# 16ch_omn_hirose_adapter.net
KiCad netlist of a schematic drawn in EAGLE
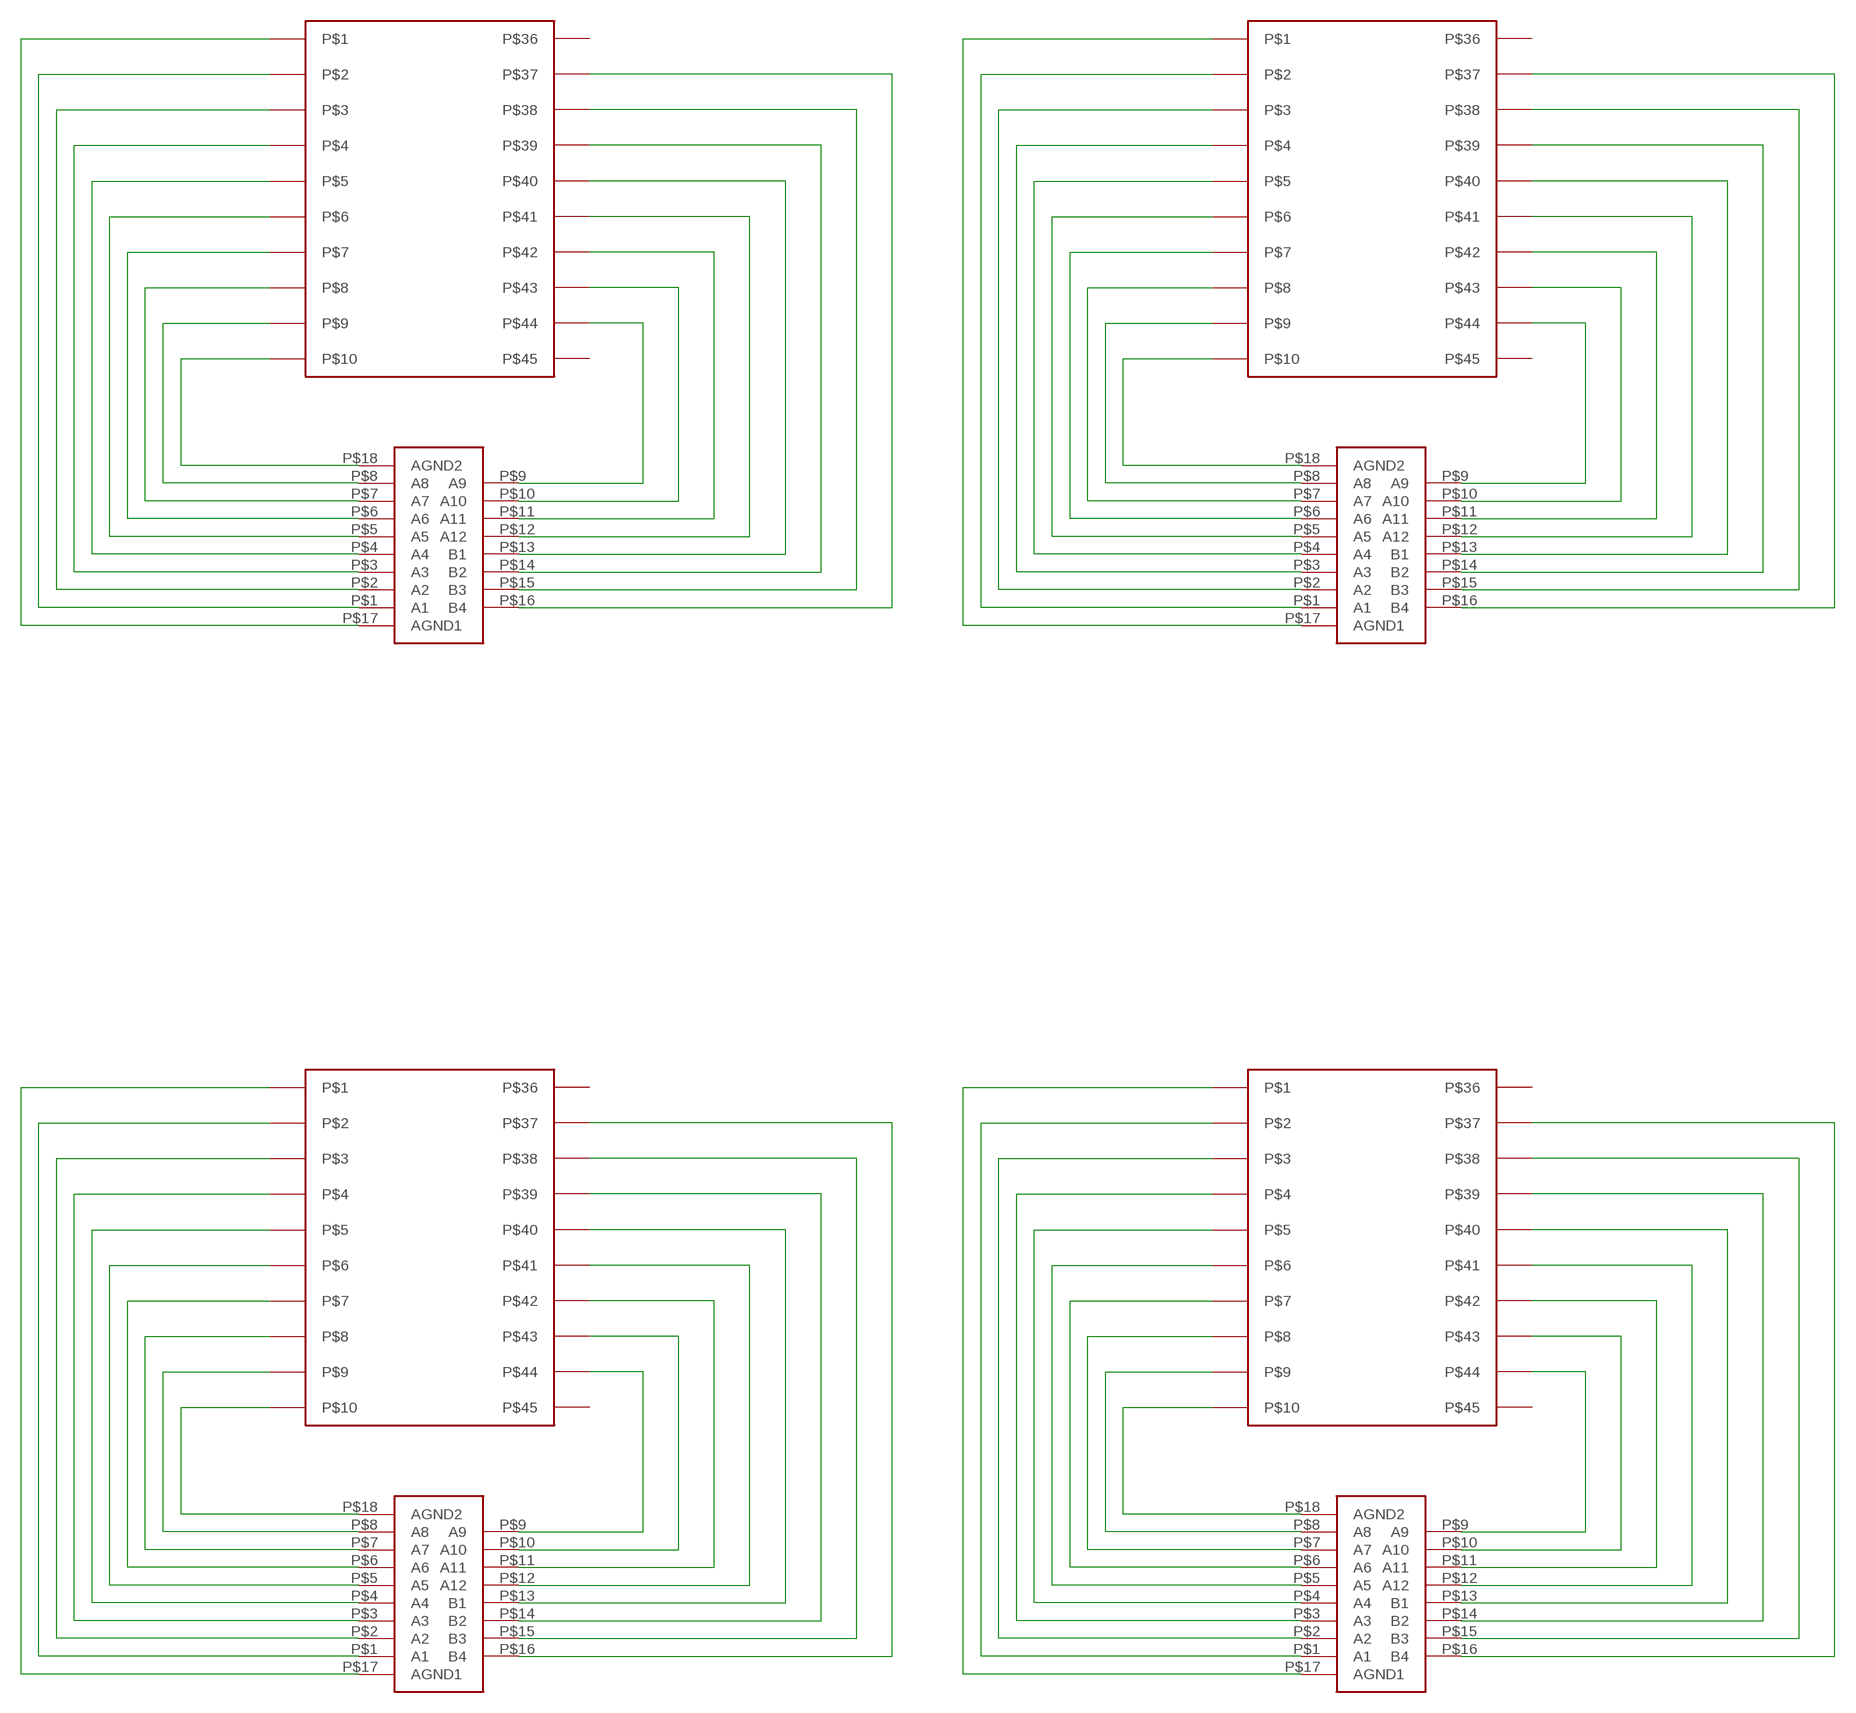
[diagram p0: schematic, sheet 1]

(export (version "E")
  (design (tool "Eeschema 10.0.6"))
  (components
    (comp (ref "U$1")
      (value "HIROSE_DF40_70PIN")
      (footprint "eagle-import:HIROSE_DF40C-70DS")
      (libsource (lib "eagle-import") (part "HIROSE_DF40_70PIN"))
    )
    (comp (ref "U$2")
      (value "OMNETICS_FE18")
      (footprint "eagle-import:OMNETICS_FE18")
      (libsource (lib "eagle-import") (part "OMNETICS_FE18"))
    )
    (comp (ref "U$3")
      (value "HIROSE_DF40_70PIN")
      (footprint "eagle-import:HIROSE_DF40C-70DS")
      (libsource (lib "eagle-import") (part "HIROSE_DF40_70PIN"))
    )
    (comp (ref "U$4")
      (value "OMNETICS_FE18")
      (footprint "eagle-import:OMNETICS_FE18")
      (libsource (lib "eagle-import") (part "OMNETICS_FE18"))
    )
    (comp (ref "U$5")
      (value "HIROSE_DF40_70PIN")
      (footprint "eagle-import:HIROSE_DF40C-70DS")
      (libsource (lib "eagle-import") (part "HIROSE_DF40_70PIN"))
    )
    (comp (ref "U$6")
      (value "OMNETICS_FE18")
      (footprint "eagle-import:OMNETICS_FE18")
      (libsource (lib "eagle-import") (part "OMNETICS_FE18"))
    )
    (comp (ref "U$7")
      (value "HIROSE_DF40_70PIN")
      (footprint "eagle-import:HIROSE_DF40C-70DS")
      (libsource (lib "eagle-import") (part "HIROSE_DF40_70PIN"))
    )
    (comp (ref "U$8")
      (value "OMNETICS_FE18")
      (footprint "eagle-import:OMNETICS_FE18")
      (libsource (lib "eagle-import") (part "OMNETICS_FE18"))
    )
  )
  (nets
    (net (code "1") (name "Net-(U$2-A1)") (class "Default")
      (node (ref "U$1") (pin "P$2") (pinfunction "P$2_P$2") (pintype "bidirectional"))
      (node (ref "U$2") (pin "P$1") (pinfunction "A1_P$1") (pintype "bidirectional"))
    )
    (net (code "2") (name "Net-(U$2-A2)") (class "Default")
      (node (ref "U$1") (pin "P$3") (pinfunction "P$3_P$3") (pintype "bidirectional"))
      (node (ref "U$2") (pin "P$2") (pinfunction "A2_P$2") (pintype "bidirectional"))
    )
    (net (code "3") (name "Net-(U$2-A3)") (class "Default")
      (node (ref "U$1") (pin "P$4") (pinfunction "P$4_P$4") (pintype "bidirectional"))
      (node (ref "U$2") (pin "P$3") (pinfunction "A3_P$3") (pintype "bidirectional"))
    )
    (net (code "4") (name "Net-(U$2-A4)") (class "Default")
      (node (ref "U$1") (pin "P$5") (pinfunction "P$5_P$5") (pintype "bidirectional"))
      (node (ref "U$2") (pin "P$4") (pinfunction "A4_P$4") (pintype "bidirectional"))
    )
    (net (code "5") (name "Net-(U$2-A5)") (class "Default")
      (node (ref "U$1") (pin "P$6") (pinfunction "P$6_P$6") (pintype "bidirectional"))
      (node (ref "U$2") (pin "P$5") (pinfunction "A5_P$5") (pintype "bidirectional"))
    )
    (net (code "6") (name "Net-(U$2-A6)") (class "Default")
      (node (ref "U$1") (pin "P$7") (pinfunction "P$7_P$7") (pintype "bidirectional"))
      (node (ref "U$2") (pin "P$6") (pinfunction "A6_P$6") (pintype "bidirectional"))
    )
    (net (code "7") (name "Net-(U$2-A7)") (class "Default")
      (node (ref "U$1") (pin "P$8") (pinfunction "P$8_P$8") (pintype "bidirectional"))
      (node (ref "U$2") (pin "P$7") (pinfunction "A7_P$7") (pintype "bidirectional"))
    )
    (net (code "8") (name "Net-(U$2-A8)") (class "Default")
      (node (ref "U$1") (pin "P$9") (pinfunction "P$9_P$9") (pintype "bidirectional"))
      (node (ref "U$2") (pin "P$8") (pinfunction "A8_P$8") (pintype "bidirectional"))
    )
    (net (code "9") (name "Net-(U$2-A9)") (class "Default")
      (node (ref "U$1") (pin "P$44") (pinfunction "P$44_P$44") (pintype "bidirectional"))
      (node (ref "U$2") (pin "P$9") (pinfunction "A9_P$9") (pintype "bidirectional"))
    )
    (net (code "10") (name "Net-(U$2-A10)") (class "Default")
      (node (ref "U$1") (pin "P$43") (pinfunction "P$43_P$43") (pintype "bidirectional"))
      (node (ref "U$2") (pin "P$10") (pinfunction "A10_P$10") (pintype "bidirectional"))
    )
    (net (code "11") (name "Net-(U$2-A11)") (class "Default")
      (node (ref "U$1") (pin "P$42") (pinfunction "P$42_P$42") (pintype "bidirectional"))
      (node (ref "U$2") (pin "P$11") (pinfunction "A11_P$11") (pintype "bidirectional"))
    )
    (net (code "12") (name "Net-(U$2-A12)") (class "Default")
      (node (ref "U$1") (pin "P$41") (pinfunction "P$41_P$41") (pintype "bidirectional"))
      (node (ref "U$2") (pin "P$12") (pinfunction "A12_P$12") (pintype "bidirectional"))
    )
    (net (code "13") (name "Net-(U$2-AGND1)") (class "Default")
      (node (ref "U$1") (pin "P$1") (pinfunction "P$1_P$1") (pintype "bidirectional"))
      (node (ref "U$2") (pin "P$17") (pinfunction "AGND1_P$17") (pintype "bidirectional"))
    )
    (net (code "14") (name "Net-(U$2-AGND2)") (class "Default")
      (node (ref "U$1") (pin "P$10") (pinfunction "P$10_P$10") (pintype "bidirectional"))
      (node (ref "U$2") (pin "P$18") (pinfunction "AGND2_P$18") (pintype "bidirectional"))
    )
    (net (code "15") (name "Net-(U$2-B1)") (class "Default")
      (node (ref "U$1") (pin "P$40") (pinfunction "P$40_P$40") (pintype "bidirectional"))
      (node (ref "U$2") (pin "P$13") (pinfunction "B1_P$13") (pintype "bidirectional"))
    )
    (net (code "16") (name "Net-(U$2-B2)") (class "Default")
      (node (ref "U$1") (pin "P$39") (pinfunction "P$39_P$39") (pintype "bidirectional"))
      (node (ref "U$2") (pin "P$14") (pinfunction "B2_P$14") (pintype "bidirectional"))
    )
    (net (code "17") (name "Net-(U$2-B3)") (class "Default")
      (node (ref "U$1") (pin "P$38") (pinfunction "P$38_P$38") (pintype "bidirectional"))
      (node (ref "U$2") (pin "P$15") (pinfunction "B3_P$15") (pintype "bidirectional"))
    )
    (net (code "18") (name "Net-(U$2-B4)") (class "Default")
      (node (ref "U$1") (pin "P$37") (pinfunction "P$37_P$37") (pintype "bidirectional"))
      (node (ref "U$2") (pin "P$16") (pinfunction "B4_P$16") (pintype "bidirectional"))
    )
    (net (code "19") (name "Net-(U$4-A1)") (class "Default")
      (node (ref "U$3") (pin "P$2") (pinfunction "P$2_P$2") (pintype "bidirectional"))
      (node (ref "U$4") (pin "P$1") (pinfunction "A1_P$1") (pintype "bidirectional"))
    )
    (net (code "20") (name "Net-(U$4-A2)") (class "Default")
      (node (ref "U$3") (pin "P$3") (pinfunction "P$3_P$3") (pintype "bidirectional"))
      (node (ref "U$4") (pin "P$2") (pinfunction "A2_P$2") (pintype "bidirectional"))
    )
    (net (code "21") (name "Net-(U$4-A3)") (class "Default")
      (node (ref "U$3") (pin "P$4") (pinfunction "P$4_P$4") (pintype "bidirectional"))
      (node (ref "U$4") (pin "P$3") (pinfunction "A3_P$3") (pintype "bidirectional"))
    )
    (net (code "22") (name "Net-(U$4-A4)") (class "Default")
      (node (ref "U$3") (pin "P$5") (pinfunction "P$5_P$5") (pintype "bidirectional"))
      (node (ref "U$4") (pin "P$4") (pinfunction "A4_P$4") (pintype "bidirectional"))
    )
    (net (code "23") (name "Net-(U$4-A5)") (class "Default")
      (node (ref "U$3") (pin "P$6") (pinfunction "P$6_P$6") (pintype "bidirectional"))
      (node (ref "U$4") (pin "P$5") (pinfunction "A5_P$5") (pintype "bidirectional"))
    )
    (net (code "24") (name "Net-(U$4-A6)") (class "Default")
      (node (ref "U$3") (pin "P$7") (pinfunction "P$7_P$7") (pintype "bidirectional"))
      (node (ref "U$4") (pin "P$6") (pinfunction "A6_P$6") (pintype "bidirectional"))
    )
    (net (code "25") (name "Net-(U$4-A7)") (class "Default")
      (node (ref "U$3") (pin "P$8") (pinfunction "P$8_P$8") (pintype "bidirectional"))
      (node (ref "U$4") (pin "P$7") (pinfunction "A7_P$7") (pintype "bidirectional"))
    )
    (net (code "26") (name "Net-(U$4-A8)") (class "Default")
      (node (ref "U$3") (pin "P$9") (pinfunction "P$9_P$9") (pintype "bidirectional"))
      (node (ref "U$4") (pin "P$8") (pinfunction "A8_P$8") (pintype "bidirectional"))
    )
    (net (code "27") (name "Net-(U$4-A9)") (class "Default")
      (node (ref "U$3") (pin "P$44") (pinfunction "P$44_P$44") (pintype "bidirectional"))
      (node (ref "U$4") (pin "P$9") (pinfunction "A9_P$9") (pintype "bidirectional"))
    )
    (net (code "28") (name "Net-(U$4-A10)") (class "Default")
      (node (ref "U$3") (pin "P$43") (pinfunction "P$43_P$43") (pintype "bidirectional"))
      (node (ref "U$4") (pin "P$10") (pinfunction "A10_P$10") (pintype "bidirectional"))
    )
    (net (code "29") (name "Net-(U$4-A11)") (class "Default")
      (node (ref "U$3") (pin "P$42") (pinfunction "P$42_P$42") (pintype "bidirectional"))
      (node (ref "U$4") (pin "P$11") (pinfunction "A11_P$11") (pintype "bidirectional"))
    )
    (net (code "30") (name "Net-(U$4-A12)") (class "Default")
      (node (ref "U$3") (pin "P$41") (pinfunction "P$41_P$41") (pintype "bidirectional"))
      (node (ref "U$4") (pin "P$12") (pinfunction "A12_P$12") (pintype "bidirectional"))
    )
    (net (code "31") (name "Net-(U$4-AGND1)") (class "Default")
      (node (ref "U$3") (pin "P$1") (pinfunction "P$1_P$1") (pintype "bidirectional"))
      (node (ref "U$4") (pin "P$17") (pinfunction "AGND1_P$17") (pintype "bidirectional"))
    )
    (net (code "32") (name "Net-(U$4-AGND2)") (class "Default")
      (node (ref "U$3") (pin "P$10") (pinfunction "P$10_P$10") (pintype "bidirectional"))
      (node (ref "U$4") (pin "P$18") (pinfunction "AGND2_P$18") (pintype "bidirectional"))
    )
    (net (code "33") (name "Net-(U$4-B1)") (class "Default")
      (node (ref "U$3") (pin "P$40") (pinfunction "P$40_P$40") (pintype "bidirectional"))
      (node (ref "U$4") (pin "P$13") (pinfunction "B1_P$13") (pintype "bidirectional"))
    )
    (net (code "34") (name "Net-(U$4-B2)") (class "Default")
      (node (ref "U$3") (pin "P$39") (pinfunction "P$39_P$39") (pintype "bidirectional"))
      (node (ref "U$4") (pin "P$14") (pinfunction "B2_P$14") (pintype "bidirectional"))
    )
    (net (code "35") (name "Net-(U$4-B3)") (class "Default")
      (node (ref "U$3") (pin "P$38") (pinfunction "P$38_P$38") (pintype "bidirectional"))
      (node (ref "U$4") (pin "P$15") (pinfunction "B3_P$15") (pintype "bidirectional"))
    )
    (net (code "36") (name "Net-(U$4-B4)") (class "Default")
      (node (ref "U$3") (pin "P$37") (pinfunction "P$37_P$37") (pintype "bidirectional"))
      (node (ref "U$4") (pin "P$16") (pinfunction "B4_P$16") (pintype "bidirectional"))
    )
    (net (code "37") (name "Net-(U$6-A1)") (class "Default")
      (node (ref "U$5") (pin "P$2") (pinfunction "P$2_P$2") (pintype "bidirectional"))
      (node (ref "U$6") (pin "P$1") (pinfunction "A1_P$1") (pintype "bidirectional"))
    )
    (net (code "38") (name "Net-(U$6-A2)") (class "Default")
      (node (ref "U$5") (pin "P$3") (pinfunction "P$3_P$3") (pintype "bidirectional"))
      (node (ref "U$6") (pin "P$2") (pinfunction "A2_P$2") (pintype "bidirectional"))
    )
    (net (code "39") (name "Net-(U$6-A3)") (class "Default")
      (node (ref "U$5") (pin "P$4") (pinfunction "P$4_P$4") (pintype "bidirectional"))
      (node (ref "U$6") (pin "P$3") (pinfunction "A3_P$3") (pintype "bidirectional"))
    )
    (net (code "40") (name "Net-(U$6-A4)") (class "Default")
      (node (ref "U$5") (pin "P$5") (pinfunction "P$5_P$5") (pintype "bidirectional"))
      (node (ref "U$6") (pin "P$4") (pinfunction "A4_P$4") (pintype "bidirectional"))
    )
    (net (code "41") (name "Net-(U$6-A5)") (class "Default")
      (node (ref "U$5") (pin "P$6") (pinfunction "P$6_P$6") (pintype "bidirectional"))
      (node (ref "U$6") (pin "P$5") (pinfunction "A5_P$5") (pintype "bidirectional"))
    )
    (net (code "42") (name "Net-(U$6-A6)") (class "Default")
      (node (ref "U$5") (pin "P$7") (pinfunction "P$7_P$7") (pintype "bidirectional"))
      (node (ref "U$6") (pin "P$6") (pinfunction "A6_P$6") (pintype "bidirectional"))
    )
    (net (code "43") (name "Net-(U$6-A7)") (class "Default")
      (node (ref "U$5") (pin "P$8") (pinfunction "P$8_P$8") (pintype "bidirectional"))
      (node (ref "U$6") (pin "P$7") (pinfunction "A7_P$7") (pintype "bidirectional"))
    )
    (net (code "44") (name "Net-(U$6-A8)") (class "Default")
      (node (ref "U$5") (pin "P$9") (pinfunction "P$9_P$9") (pintype "bidirectional"))
      (node (ref "U$6") (pin "P$8") (pinfunction "A8_P$8") (pintype "bidirectional"))
    )
    (net (code "45") (name "Net-(U$6-A9)") (class "Default")
      (node (ref "U$5") (pin "P$44") (pinfunction "P$44_P$44") (pintype "bidirectional"))
      (node (ref "U$6") (pin "P$9") (pinfunction "A9_P$9") (pintype "bidirectional"))
    )
    (net (code "46") (name "Net-(U$6-A10)") (class "Default")
      (node (ref "U$5") (pin "P$43") (pinfunction "P$43_P$43") (pintype "bidirectional"))
      (node (ref "U$6") (pin "P$10") (pinfunction "A10_P$10") (pintype "bidirectional"))
    )
    (net (code "47") (name "Net-(U$6-A11)") (class "Default")
      (node (ref "U$5") (pin "P$42") (pinfunction "P$42_P$42") (pintype "bidirectional"))
      (node (ref "U$6") (pin "P$11") (pinfunction "A11_P$11") (pintype "bidirectional"))
    )
    (net (code "48") (name "Net-(U$6-A12)") (class "Default")
      (node (ref "U$5") (pin "P$41") (pinfunction "P$41_P$41") (pintype "bidirectional"))
      (node (ref "U$6") (pin "P$12") (pinfunction "A12_P$12") (pintype "bidirectional"))
    )
    (net (code "49") (name "Net-(U$6-AGND1)") (class "Default")
      (node (ref "U$5") (pin "P$1") (pinfunction "P$1_P$1") (pintype "bidirectional"))
      (node (ref "U$6") (pin "P$17") (pinfunction "AGND1_P$17") (pintype "bidirectional"))
    )
    (net (code "50") (name "Net-(U$6-AGND2)") (class "Default")
      (node (ref "U$5") (pin "P$10") (pinfunction "P$10_P$10") (pintype "bidirectional"))
      (node (ref "U$6") (pin "P$18") (pinfunction "AGND2_P$18") (pintype "bidirectional"))
    )
    (net (code "51") (name "Net-(U$6-B1)") (class "Default")
      (node (ref "U$5") (pin "P$40") (pinfunction "P$40_P$40") (pintype "bidirectional"))
      (node (ref "U$6") (pin "P$13") (pinfunction "B1_P$13") (pintype "bidirectional"))
    )
    (net (code "52") (name "Net-(U$6-B2)") (class "Default")
      (node (ref "U$5") (pin "P$39") (pinfunction "P$39_P$39") (pintype "bidirectional"))
      (node (ref "U$6") (pin "P$14") (pinfunction "B2_P$14") (pintype "bidirectional"))
    )
    (net (code "53") (name "Net-(U$6-B3)") (class "Default")
      (node (ref "U$5") (pin "P$38") (pinfunction "P$38_P$38") (pintype "bidirectional"))
      (node (ref "U$6") (pin "P$15") (pinfunction "B3_P$15") (pintype "bidirectional"))
    )
    (net (code "54") (name "Net-(U$6-B4)") (class "Default")
      (node (ref "U$5") (pin "P$37") (pinfunction "P$37_P$37") (pintype "bidirectional"))
      (node (ref "U$6") (pin "P$16") (pinfunction "B4_P$16") (pintype "bidirectional"))
    )
    (net (code "55") (name "Net-(U$8-A1)") (class "Default")
      (node (ref "U$7") (pin "P$2") (pinfunction "P$2_P$2") (pintype "bidirectional"))
      (node (ref "U$8") (pin "P$1") (pinfunction "A1_P$1") (pintype "bidirectional"))
    )
    (net (code "56") (name "Net-(U$8-A2)") (class "Default")
      (node (ref "U$7") (pin "P$3") (pinfunction "P$3_P$3") (pintype "bidirectional"))
      (node (ref "U$8") (pin "P$2") (pinfunction "A2_P$2") (pintype "bidirectional"))
    )
    (net (code "57") (name "Net-(U$8-A3)") (class "Default")
      (node (ref "U$7") (pin "P$4") (pinfunction "P$4_P$4") (pintype "bidirectional"))
      (node (ref "U$8") (pin "P$3") (pinfunction "A3_P$3") (pintype "bidirectional"))
    )
    (net (code "58") (name "Net-(U$8-A4)") (class "Default")
      (node (ref "U$7") (pin "P$5") (pinfunction "P$5_P$5") (pintype "bidirectional"))
      (node (ref "U$8") (pin "P$4") (pinfunction "A4_P$4") (pintype "bidirectional"))
    )
    (net (code "59") (name "Net-(U$8-A5)") (class "Default")
      (node (ref "U$7") (pin "P$6") (pinfunction "P$6_P$6") (pintype "bidirectional"))
      (node (ref "U$8") (pin "P$5") (pinfunction "A5_P$5") (pintype "bidirectional"))
    )
    (net (code "60") (name "Net-(U$8-A6)") (class "Default")
      (node (ref "U$7") (pin "P$7") (pinfunction "P$7_P$7") (pintype "bidirectional"))
      (node (ref "U$8") (pin "P$6") (pinfunction "A6_P$6") (pintype "bidirectional"))
    )
    (net (code "61") (name "Net-(U$8-A7)") (class "Default")
      (node (ref "U$7") (pin "P$8") (pinfunction "P$8_P$8") (pintype "bidirectional"))
      (node (ref "U$8") (pin "P$7") (pinfunction "A7_P$7") (pintype "bidirectional"))
    )
    (net (code "62") (name "Net-(U$8-A8)") (class "Default")
      (node (ref "U$7") (pin "P$9") (pinfunction "P$9_P$9") (pintype "bidirectional"))
      (node (ref "U$8") (pin "P$8") (pinfunction "A8_P$8") (pintype "bidirectional"))
    )
    (net (code "63") (name "Net-(U$8-A9)") (class "Default")
      (node (ref "U$7") (pin "P$44") (pinfunction "P$44_P$44") (pintype "bidirectional"))
      (node (ref "U$8") (pin "P$9") (pinfunction "A9_P$9") (pintype "bidirectional"))
    )
    (net (code "64") (name "Net-(U$8-A10)") (class "Default")
      (node (ref "U$7") (pin "P$43") (pinfunction "P$43_P$43") (pintype "bidirectional"))
      (node (ref "U$8") (pin "P$10") (pinfunction "A10_P$10") (pintype "bidirectional"))
    )
    (net (code "65") (name "Net-(U$8-A11)") (class "Default")
      (node (ref "U$7") (pin "P$42") (pinfunction "P$42_P$42") (pintype "bidirectional"))
      (node (ref "U$8") (pin "P$11") (pinfunction "A11_P$11") (pintype "bidirectional"))
    )
    (net (code "66") (name "Net-(U$8-A12)") (class "Default")
      (node (ref "U$7") (pin "P$41") (pinfunction "P$41_P$41") (pintype "bidirectional"))
      (node (ref "U$8") (pin "P$12") (pinfunction "A12_P$12") (pintype "bidirectional"))
    )
    (net (code "67") (name "Net-(U$8-AGND1)") (class "Default")
      (node (ref "U$7") (pin "P$1") (pinfunction "P$1_P$1") (pintype "bidirectional"))
      (node (ref "U$8") (pin "P$17") (pinfunction "AGND1_P$17") (pintype "bidirectional"))
    )
    (net (code "68") (name "Net-(U$8-AGND2)") (class "Default")
      (node (ref "U$7") (pin "P$10") (pinfunction "P$10_P$10") (pintype "bidirectional"))
      (node (ref "U$8") (pin "P$18") (pinfunction "AGND2_P$18") (pintype "bidirectional"))
    )
    (net (code "69") (name "Net-(U$8-B1)") (class "Default")
      (node (ref "U$7") (pin "P$40") (pinfunction "P$40_P$40") (pintype "bidirectional"))
      (node (ref "U$8") (pin "P$13") (pinfunction "B1_P$13") (pintype "bidirectional"))
    )
    (net (code "70") (name "Net-(U$8-B2)") (class "Default")
      (node (ref "U$7") (pin "P$39") (pinfunction "P$39_P$39") (pintype "bidirectional"))
      (node (ref "U$8") (pin "P$14") (pinfunction "B2_P$14") (pintype "bidirectional"))
    )
    (net (code "71") (name "Net-(U$8-B3)") (class "Default")
      (node (ref "U$7") (pin "P$38") (pinfunction "P$38_P$38") (pintype "bidirectional"))
      (node (ref "U$8") (pin "P$15") (pinfunction "B3_P$15") (pintype "bidirectional"))
    )
    (net (code "72") (name "Net-(U$8-B4)") (class "Default")
      (node (ref "U$7") (pin "P$37") (pinfunction "P$37_P$37") (pintype "bidirectional"))
      (node (ref "U$8") (pin "P$16") (pinfunction "B4_P$16") (pintype "bidirectional"))
    )
    (net (code "73") (name "unconnected-(U$1-PadP$36)") (class "Default")
      (node (ref "U$1") (pin "P$36") (pinfunction "P$36_P$36") (pintype "bidirectional"))
    )
    (net (code "74") (name "unconnected-(U$1-PadP$45)") (class "Default")
      (node (ref "U$1") (pin "P$45") (pinfunction "P$45_P$45") (pintype "bidirectional"))
    )
    (net (code "75") (name "unconnected-(U$3-PadP$36)") (class "Default")
      (node (ref "U$3") (pin "P$36") (pinfunction "P$36_P$36") (pintype "bidirectional"))
    )
    (net (code "76") (name "unconnected-(U$3-PadP$45)") (class "Default")
      (node (ref "U$3") (pin "P$45") (pinfunction "P$45_P$45") (pintype "bidirectional"))
    )
    (net (code "77") (name "unconnected-(U$5-PadP$36)") (class "Default")
      (node (ref "U$5") (pin "P$36") (pinfunction "P$36_P$36") (pintype "bidirectional"))
    )
    (net (code "78") (name "unconnected-(U$5-PadP$45)") (class "Default")
      (node (ref "U$5") (pin "P$45") (pinfunction "P$45_P$45") (pintype "bidirectional"))
    )
    (net (code "79") (name "unconnected-(U$7-PadP$36)") (class "Default")
      (node (ref "U$7") (pin "P$36") (pinfunction "P$36_P$36") (pintype "bidirectional"))
    )
    (net (code "80") (name "unconnected-(U$7-PadP$45)") (class "Default")
      (node (ref "U$7") (pin "P$45") (pinfunction "P$45_P$45") (pintype "bidirectional"))
    )
  )
)
